# H3BR20.net
KiCad netlist of a schematic drawn in EAGLE
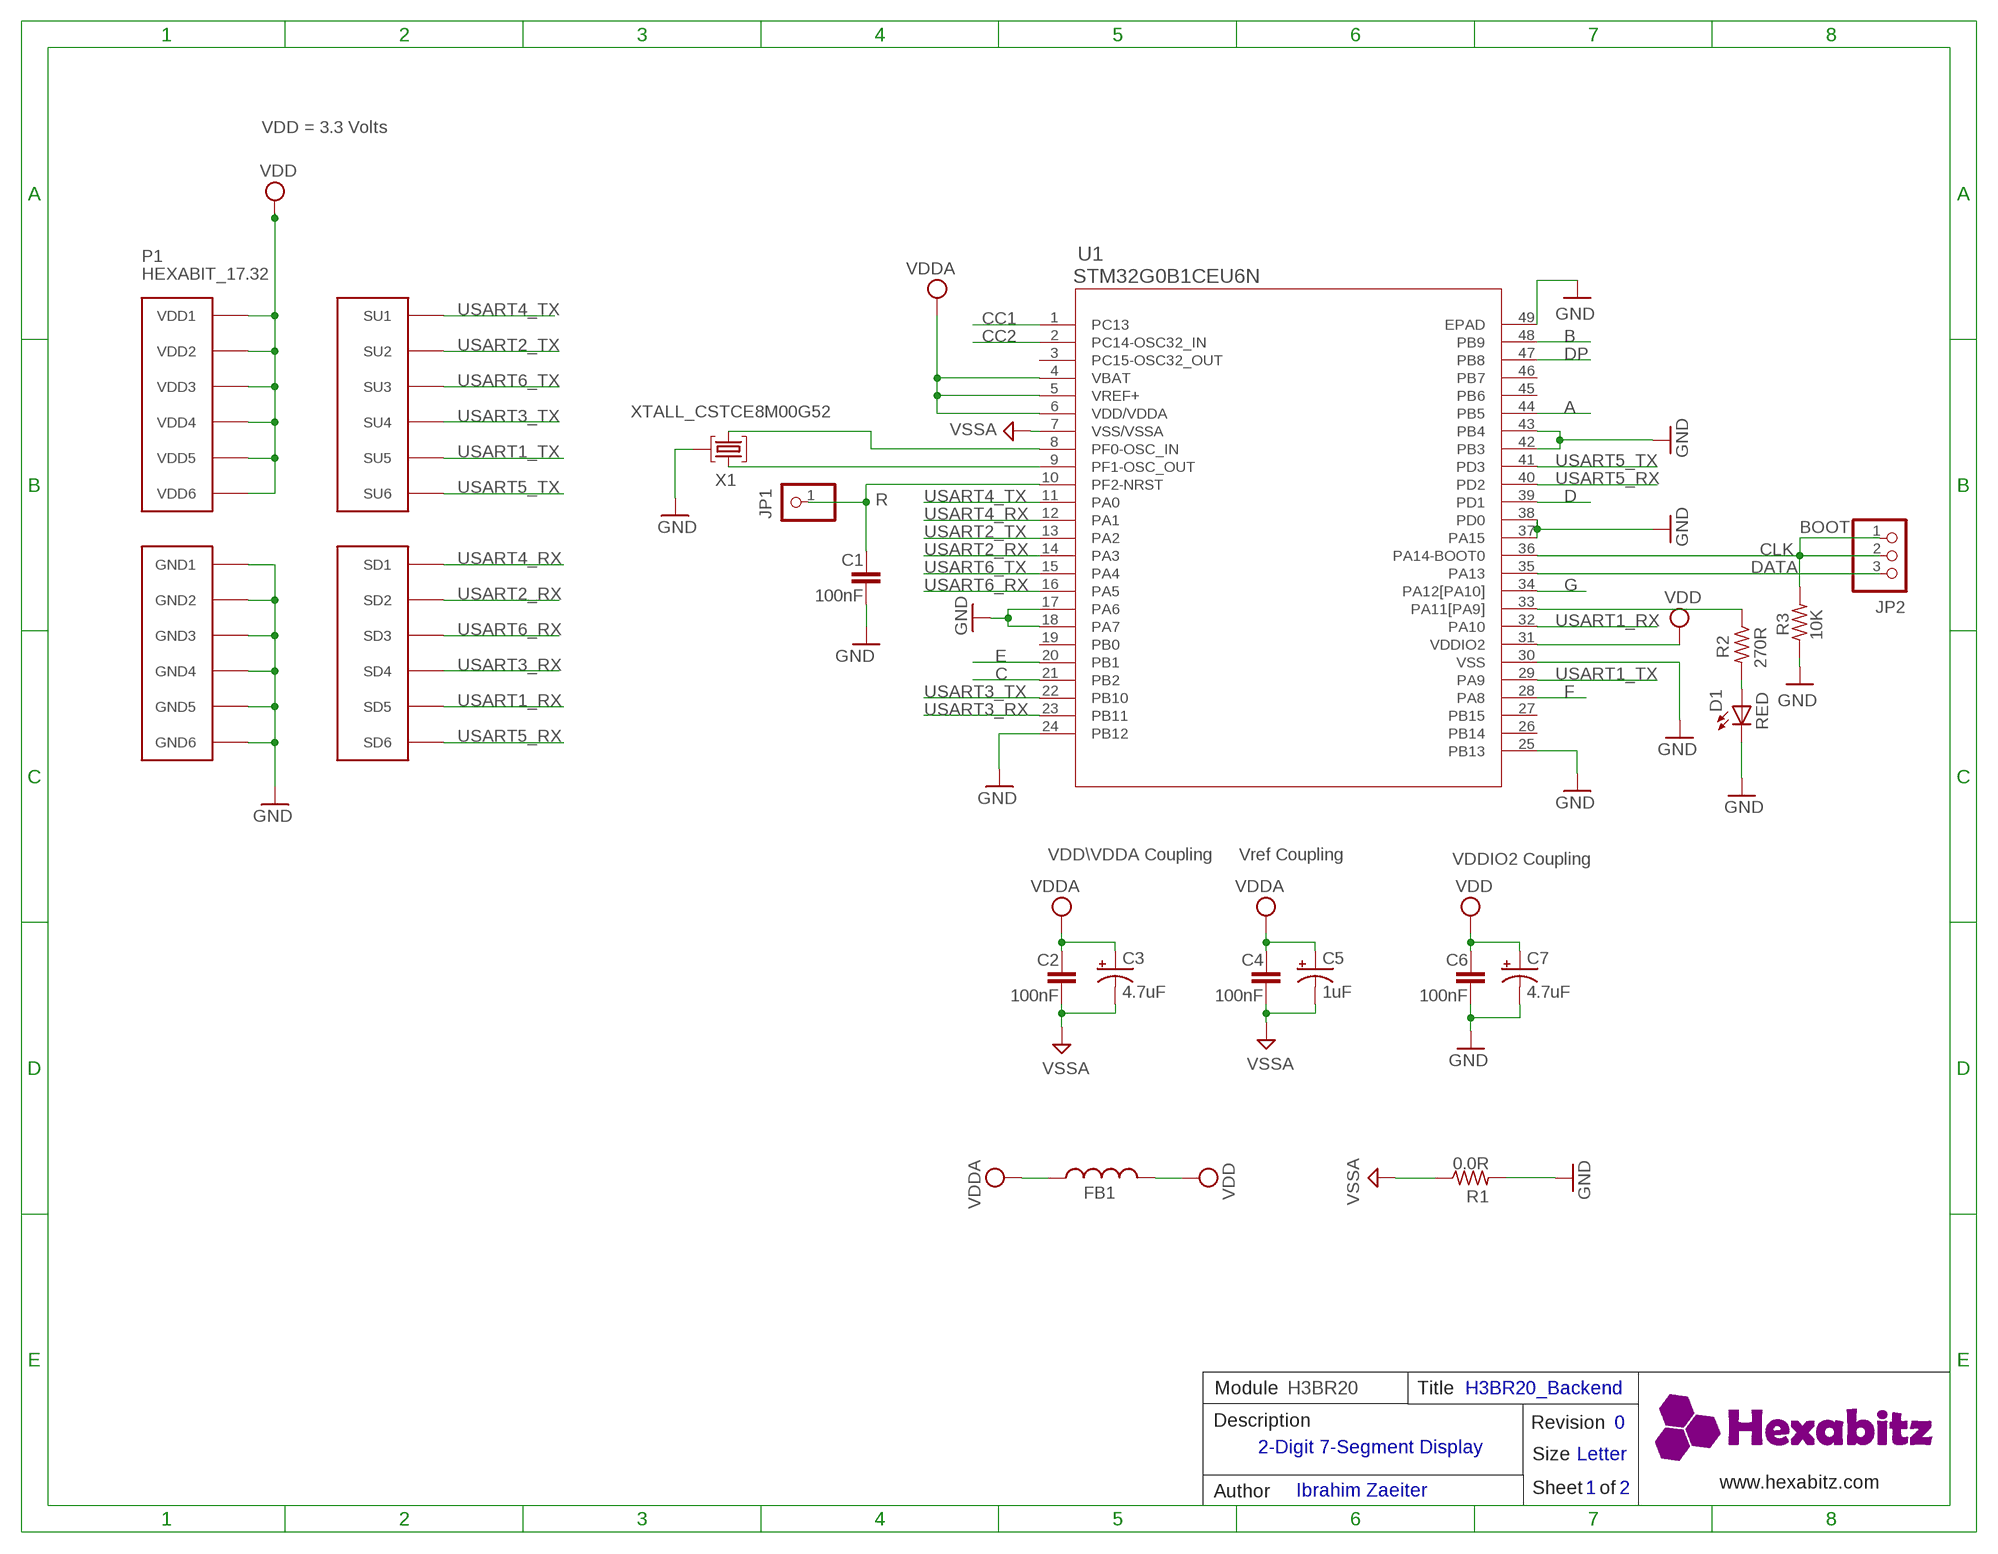
[diagram p0: schematic, sheet 1]
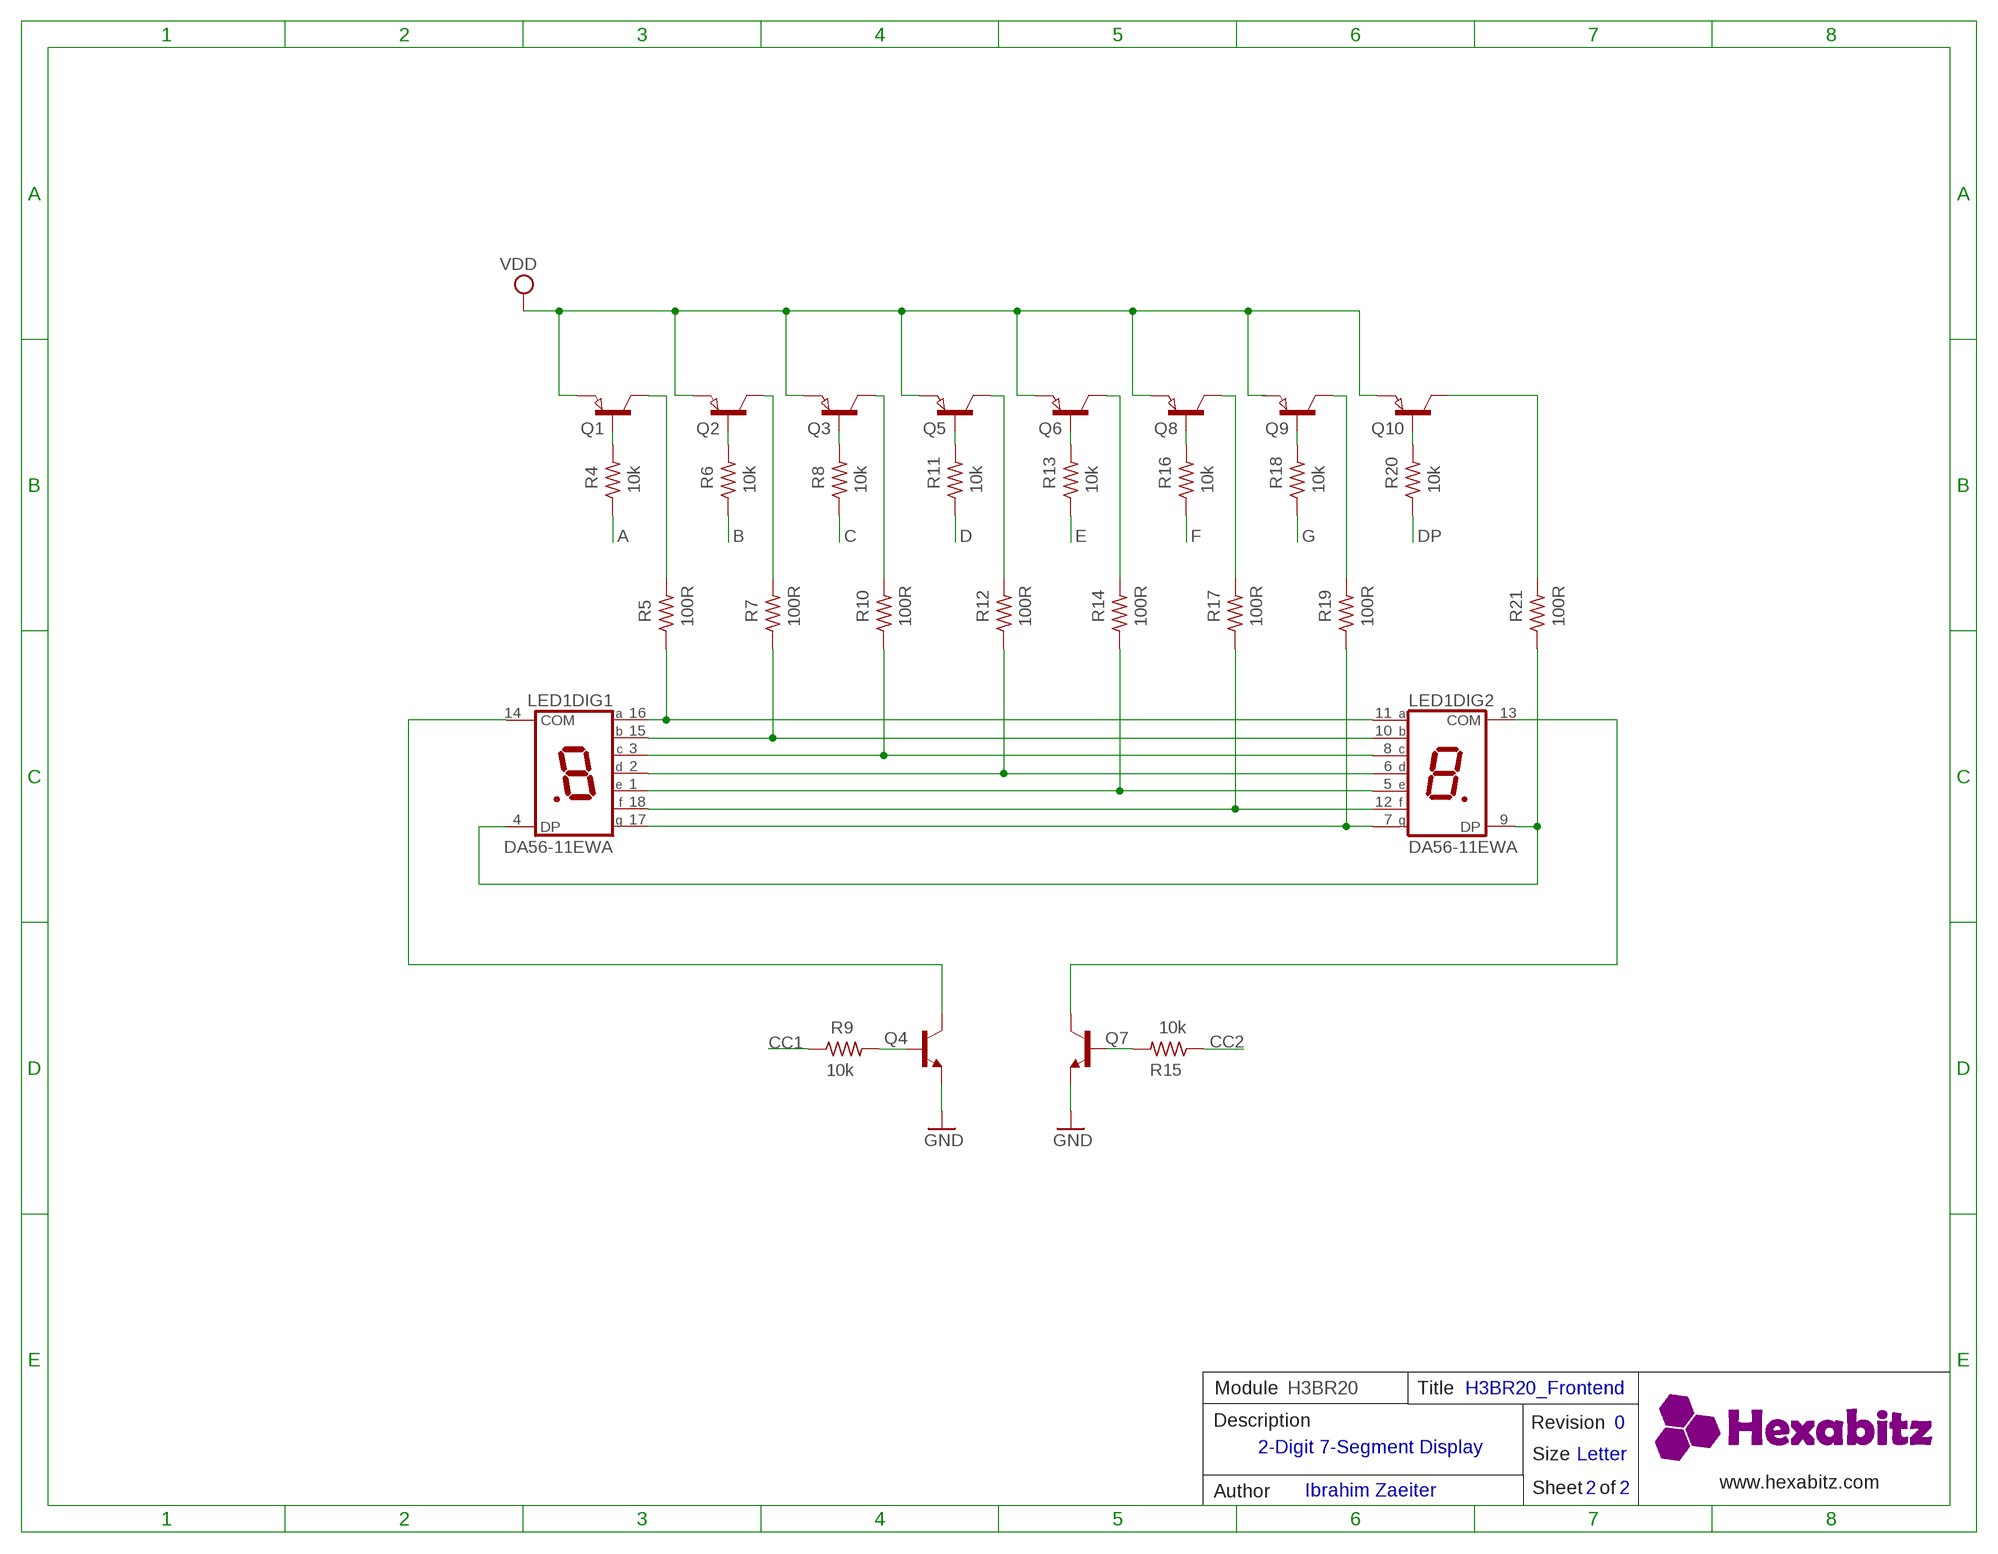
[diagram p1: schematic, sheet 2]

(export (version "E")
  (design (tool "Eeschema 10.0.6"))
  (components
    (comp (ref "LED1")
      (value "DA56-11EWA")
      (footprint "eagle-import:DA56")
      (fields (field (name "MF") "Lite-On") (field (name "MPN") "LTD-6940HR"))
      (libsource (lib "eagle-import") (part "DA56-11EWA"))
    )
    (comp (ref "Q1")
      (value "SEMICON-SMD-IPC_PNP-TRANSISTOR_SOT23")
      (footprint "eagle-import:SEMICON-SMD-IPC_SOT23")
      (libsource (lib "eagle-import") (part "SEMICON-SMD-IPC_PNP-TRANSISTOR_SOT23"))
    )
    (comp (ref "Q2")
      (value "SEMICON-SMD-IPC_PNP-TRANSISTOR_SOT23")
      (footprint "eagle-import:SEMICON-SMD-IPC_SOT23")
      (libsource (lib "eagle-import") (part "SEMICON-SMD-IPC_PNP-TRANSISTOR_SOT23"))
    )
    (comp (ref "Q3")
      (value "SEMICON-SMD-IPC_PNP-TRANSISTOR_SOT23")
      (footprint "eagle-import:SEMICON-SMD-IPC_SOT23")
      (libsource (lib "eagle-import") (part "SEMICON-SMD-IPC_PNP-TRANSISTOR_SOT23"))
    )
    (comp (ref "Q4")
      (value "MMBT3904LT1")
      (footprint "eagle-import:MMBT3904LT1")
      (libsource (lib "eagle-import") (part "MMBT3904LT1"))
    )
    (comp (ref "Q5")
      (value "SEMICON-SMD-IPC_PNP-TRANSISTOR_SOT23")
      (footprint "eagle-import:SEMICON-SMD-IPC_SOT23")
      (libsource (lib "eagle-import") (part "SEMICON-SMD-IPC_PNP-TRANSISTOR_SOT23"))
    )
    (comp (ref "Q6")
      (value "SEMICON-SMD-IPC_PNP-TRANSISTOR_SOT23")
      (footprint "eagle-import:SEMICON-SMD-IPC_SOT23")
      (libsource (lib "eagle-import") (part "SEMICON-SMD-IPC_PNP-TRANSISTOR_SOT23"))
    )
    (comp (ref "Q7")
      (value "MMBT3904LT1")
      (footprint "eagle-import:MMBT3904LT1")
      (libsource (lib "eagle-import") (part "MMBT3904LT1"))
    )
    (comp (ref "Q8")
      (value "SEMICON-SMD-IPC_PNP-TRANSISTOR_SOT23")
      (footprint "eagle-import:SEMICON-SMD-IPC_SOT23")
      (libsource (lib "eagle-import") (part "SEMICON-SMD-IPC_PNP-TRANSISTOR_SOT23"))
    )
    (comp (ref "Q9")
      (value "SEMICON-SMD-IPC_PNP-TRANSISTOR_SOT23")
      (footprint "eagle-import:SEMICON-SMD-IPC_SOT23")
      (libsource (lib "eagle-import") (part "SEMICON-SMD-IPC_PNP-TRANSISTOR_SOT23"))
    )
    (comp (ref "Q10")
      (value "SEMICON-SMD-IPC_PNP-TRANSISTOR_SOT23")
      (footprint "eagle-import:SEMICON-SMD-IPC_SOT23")
      (libsource (lib "eagle-import") (part "SEMICON-SMD-IPC_PNP-TRANSISTOR_SOT23"))
    )
    (comp (ref "R4")
      (value "10k")
      (footprint "eagle-import:R-0402")
      (libsource (lib "eagle-import") (part "R-0402"))
    )
    (comp (ref "R5")
      (value "100R")
      (footprint "eagle-import:R-0402")
      (libsource (lib "eagle-import") (part "R-0402"))
    )
    (comp (ref "R6")
      (value "10k")
      (footprint "eagle-import:R-0402")
      (libsource (lib "eagle-import") (part "R-0402"))
    )
    (comp (ref "R7")
      (value "100R")
      (footprint "eagle-import:R-0402")
      (libsource (lib "eagle-import") (part "R-0402"))
    )
    (comp (ref "R8")
      (value "10k")
      (footprint "eagle-import:R-0402")
      (libsource (lib "eagle-import") (part "R-0402"))
    )
    (comp (ref "R9")
      (value "10k")
      (footprint "eagle-import:R-0402")
      (libsource (lib "eagle-import") (part "R-0402"))
    )
    (comp (ref "R10")
      (value "100R")
      (footprint "eagle-import:R-0402")
      (libsource (lib "eagle-import") (part "R-0402"))
    )
    (comp (ref "R11")
      (value "10k")
      (footprint "eagle-import:R-0402")
      (libsource (lib "eagle-import") (part "R-0402"))
    )
    (comp (ref "R12")
      (value "100R")
      (footprint "eagle-import:R-0402")
      (libsource (lib "eagle-import") (part "R-0402"))
    )
    (comp (ref "R13")
      (value "10k")
      (footprint "eagle-import:R-0402")
      (libsource (lib "eagle-import") (part "R-0402"))
    )
    (comp (ref "R14")
      (value "100R")
      (footprint "eagle-import:R-0402")
      (libsource (lib "eagle-import") (part "R-0402"))
    )
    (comp (ref "R15")
      (value "10k")
      (footprint "eagle-import:R-0402")
      (libsource (lib "eagle-import") (part "R-0402"))
    )
    (comp (ref "R16")
      (value "10k")
      (footprint "eagle-import:R-0402")
      (libsource (lib "eagle-import") (part "R-0402"))
    )
    (comp (ref "R17")
      (value "100R")
      (footprint "eagle-import:R-0402")
      (libsource (lib "eagle-import") (part "R-0402"))
    )
    (comp (ref "R18")
      (value "10k")
      (footprint "eagle-import:R-0402")
      (libsource (lib "eagle-import") (part "R-0402"))
    )
    (comp (ref "R19")
      (value "100R")
      (footprint "eagle-import:R-0402")
      (libsource (lib "eagle-import") (part "R-0402"))
    )
    (comp (ref "R20")
      (value "10k")
      (footprint "eagle-import:R-0402")
      (libsource (lib "eagle-import") (part "R-0402"))
    )
    (comp (ref "R21")
      (value "100R")
      (footprint "eagle-import:R-0402")
      (libsource (lib "eagle-import") (part "R-0402"))
    )
    (comp (ref "C1")
      (value "100nF")
      (footprint "eagle-import:C-0402")
      (libsource (lib "eagle-import") (part "C-0402"))
    )
    (comp (ref "C2")
      (value "100nF")
      (footprint "eagle-import:C-0402")
      (libsource (lib "eagle-import") (part "C-0402"))
    )
    (comp (ref "C3")
      (value "4.7uF")
      (footprint "eagle-import:C-0805-POL")
      (libsource (lib "eagle-import") (part "C-0805-POL"))
    )
    (comp (ref "C4")
      (value "100nF")
      (footprint "eagle-import:C-0402")
      (libsource (lib "eagle-import") (part "C-0402"))
    )
    (comp (ref "C5")
      (value "1uF")
      (footprint "eagle-import:C-0805-POL")
      (libsource (lib "eagle-import") (part "C-0805-POL"))
    )
    (comp (ref "C6")
      (value "100nF")
      (footprint "eagle-import:C-0402")
      (libsource (lib "eagle-import") (part "C-0402"))
    )
    (comp (ref "C7")
      (value "4.7uF")
      (footprint "eagle-import:C-0805-POL")
      (libsource (lib "eagle-import") (part "C-0805-POL"))
    )
    (comp (ref "D1")
      (value "RED")
      (footprint "eagle-import:VLMS1300-GS08")
      (fields
        (field (name "MPN") "VLMS1300-GS08")
        (field (name "MFN") "Vishay")
        (field (name "MPN_1") "VLMS1300-GS08")
        (field (name "OCTOPART_URL") "https://octopart.com/vlms1300-gs08-vishay-21709201?r=sp&s=_gcP4_q8T1SC6PJQPTQ9yA")
      )
      (libsource (lib "eagle-import") (part "VLMS1300-GS08"))
    )
    (comp (ref "FB1")
      (value "FB-0603")
      (footprint "eagle-import:FB-0603")
      (libsource (lib "eagle-import") (part "FB-0603"))
    )
    (comp (ref "JP1")
      (value "R")
      (footprint "eagle-import:1X01")
      (fields (field (name "MPN") "87227-1"))
      (libsource (lib "eagle-import") (part "PINHD-1X1"))
    )
    (comp (ref "JP2")
      (value "PINHD-1X3")
      (footprint "eagle-import:1X03")
      (libsource (lib "eagle-import") (part "PINHD-1X3"))
    )
    (comp (ref "P1")
      (value "HEXABIT_17.32")
      (footprint "eagle-import:HEXABIT_17.32")
      (libsource (lib "eagle-import") (part "HEXABIT_?17.32"))
    )
    (comp (ref "R1")
      (value "0.0R")
      (footprint "eagle-import:R-0402")
      (libsource (lib "eagle-import") (part "R-0402"))
    )
    (comp (ref "R2")
      (value "270R")
      (footprint "eagle-import:R-0603")
      (libsource (lib "eagle-import") (part "R-0603"))
    )
    (comp (ref "R3")
      (value "10K")
      (footprint "eagle-import:R-0402")
      (libsource (lib "eagle-import") (part "R-0402"))
    )
    (comp (ref "U1")
      (value "STM32G0B1CEU6N")
      (footprint "eagle-import:QFN_B1CEU6_STM-L")
      (libsource (lib "eagle-import") (part "STM32G0B1CEU6N"))
    )
    (comp (ref "X1")
      (value "XTALL_CSTCE8M00G52")
      (footprint "eagle-import:XTALL_CSTCE8M00G52")
      (fields (field (name "MPN") "CSTCE8M00G52Z-R0"))
      (libsource (lib "eagle-import") (part "XTALL_CSTCE8M00G52"))
    )
  )
  (nets
    (net (code "1") (name "A") (class "Default")
      (node (ref "R4") (pin "1") (pinfunction "1_1") (pintype "passive"))
      (node (ref "U1") (pin "44") (pinfunction "PB5_44") (pintype "bidirectional"))
    )
    (net (code "2") (name "B") (class "Default")
      (node (ref "R6") (pin "1") (pinfunction "1_1") (pintype "passive"))
      (node (ref "U1") (pin "48") (pinfunction "PB9_48") (pintype "bidirectional"))
    )
    (net (code "3") (name "C") (class "Default")
      (node (ref "R8") (pin "1") (pinfunction "1_1") (pintype "passive"))
      (node (ref "U1") (pin "21") (pinfunction "PB2_21") (pintype "bidirectional"))
    )
    (net (code "4") (name "CC1") (class "Default")
      (node (ref "R9") (pin "1") (pinfunction "1_1") (pintype "passive"))
      (node (ref "U1") (pin "1") (pinfunction "PC13_1") (pintype "bidirectional"))
    )
    (net (code "5") (name "CC2") (class "Default")
      (node (ref "R15") (pin "1") (pinfunction "1_1") (pintype "passive"))
      (node (ref "U1") (pin "2") (pinfunction "PC14-OSC32_IN_2") (pintype "bidirectional"))
    )
    (net (code "6") (name "CLK") (class "Default")
      (node (ref "JP2") (pin "1") (pinfunction "1_1") (pintype "passive"))
      (node (ref "JP2") (pin "2") (pinfunction "2_2") (pintype "passive"))
      (node (ref "R3") (pin "2") (pinfunction "2_2") (pintype "passive"))
      (node (ref "U1") (pin "36") (pinfunction "PA14-BOOT0_36") (pintype "bidirectional"))
    )
    (net (code "7") (name "D") (class "Default")
      (node (ref "R11") (pin "1") (pinfunction "1_1") (pintype "passive"))
      (node (ref "U1") (pin "39") (pinfunction "PD1_39") (pintype "bidirectional"))
    )
    (net (code "8") (name "DATA") (class "Default")
      (node (ref "JP2") (pin "3") (pinfunction "3_3") (pintype "passive"))
      (node (ref "U1") (pin "35") (pinfunction "PA13_35") (pintype "bidirectional"))
    )
    (net (code "9") (name "DP") (class "Default")
      (node (ref "R20") (pin "1") (pinfunction "1_1") (pintype "passive"))
      (node (ref "U1") (pin "47") (pinfunction "PB8_47") (pintype "bidirectional"))
    )
    (net (code "10") (name "E") (class "Default")
      (node (ref "R13") (pin "1") (pinfunction "1_1") (pintype "passive"))
      (node (ref "U1") (pin "20") (pinfunction "PB1_20") (pintype "bidirectional"))
    )
    (net (code "11") (name "F") (class "Default")
      (node (ref "R16") (pin "1") (pinfunction "1_1") (pintype "passive"))
      (node (ref "U1") (pin "28") (pinfunction "PA8_28") (pintype "bidirectional"))
    )
    (net (code "12") (name "G") (class "Default")
      (node (ref "R18") (pin "1") (pinfunction "1_1") (pintype "passive"))
      (node (ref "U1") (pin "34") (pinfunction "PA12[PA10]_34") (pintype "bidirectional"))
    )
    (net (code "13") (name "GND") (class "Default")
      (node (ref "C1") (pin "2") (pinfunction "2_2") (pintype "passive"))
      (node (ref "C6") (pin "2") (pinfunction "2_2") (pintype "passive"))
      (node (ref "C7") (pin "2") (pinfunction "-_2") (pintype "passive"))
      (node (ref "D1") (pin "C") (pinfunction "C_C") (pintype "passive"))
      (node (ref "P1") (pin "PAD_PD10") (pinfunction "GND4_PAD_PD10") (pintype "power_in"))
      (node (ref "P1") (pin "PAD_PD11") (pinfunction "GND5_PAD_PD11") (pintype "power_in"))
      (node (ref "P1") (pin "PAD_PD12") (pinfunction "GND6_PAD_PD12") (pintype "power_in"))
      (node (ref "P1") (pin "PAD_PD7") (pinfunction "GND1_PAD_PD7") (pintype "power_in"))
      (node (ref "P1") (pin "PAD_PD8") (pinfunction "GND2_PAD_PD8") (pintype "power_in"))
      (node (ref "P1") (pin "PAD_PD9") (pinfunction "GND3_PAD_PD9") (pintype "power_in"))
      (node (ref "Q4") (pin "2") (pinfunction "E_2") (pintype "passive"))
      (node (ref "Q7") (pin "2") (pinfunction "E_2") (pintype "passive"))
      (node (ref "R1") (pin "2") (pinfunction "2_2") (pintype "passive"))
      (node (ref "R3") (pin "1") (pinfunction "1_1") (pintype "passive"))
      (node (ref "U1") (pin "17") (pinfunction "PA6_17") (pintype "bidirectional"))
      (node (ref "U1") (pin "18") (pinfunction "PA7_18") (pintype "bidirectional"))
      (node (ref "U1") (pin "24") (pinfunction "PB12_24") (pintype "bidirectional"))
      (node (ref "U1") (pin "25") (pinfunction "PB13_25") (pintype "bidirectional"))
      (node (ref "U1") (pin "30") (pinfunction "VSS_30") (pintype "passive"))
      (node (ref "U1") (pin "37") (pinfunction "PA15_37") (pintype "bidirectional"))
      (node (ref "U1") (pin "38") (pinfunction "PD0_38") (pintype "bidirectional"))
      (node (ref "U1") (pin "42") (pinfunction "PB3_42") (pintype "bidirectional"))
      (node (ref "U1") (pin "43") (pinfunction "PB4_43") (pintype "bidirectional"))
      (node (ref "U1") (pin "49") (pinfunction "EPAD_49") (pintype "passive"))
      (node (ref "X1") (pin "P$2") (pinfunction "2_P$2") (pintype "passive"))
    )
    (net (code "14") (name "Net-(D1-PadA)") (class "Default")
      (node (ref "D1") (pin "A") (pinfunction "A_A") (pintype "passive"))
      (node (ref "R2") (pin "2") (pinfunction "2_2") (pintype "passive"))
    )
    (net (code "15") (name "Net-(LED1A-A)") (class "Default")
      (node (ref "LED1") (pin "11") (pinfunction "A_11") (pintype "passive"))
      (node (ref "LED1") (pin "16") (pinfunction "A_16") (pintype "passive"))
      (node (ref "R5") (pin "1") (pinfunction "1_1") (pintype "passive"))
    )
    (net (code "16") (name "Net-(LED1A-B)") (class "Default")
      (node (ref "LED1") (pin "10") (pinfunction "B_10") (pintype "passive"))
      (node (ref "LED1") (pin "15") (pinfunction "B_15") (pintype "passive"))
      (node (ref "R7") (pin "1") (pinfunction "1_1") (pintype "passive"))
    )
    (net (code "17") (name "Net-(LED1A-C)") (class "Default")
      (node (ref "LED1") (pin "3") (pinfunction "C_3") (pintype "passive"))
      (node (ref "LED1") (pin "8") (pinfunction "C_8") (pintype "passive"))
      (node (ref "R10") (pin "1") (pinfunction "1_1") (pintype "passive"))
    )
    (net (code "18") (name "Net-(LED1A-COM)") (class "Default")
      (node (ref "LED1") (pin "14") (pinfunction "COM_14") (pintype "passive"))
      (node (ref "Q4") (pin "3") (pinfunction "C_3") (pintype "passive"))
    )
    (net (code "19") (name "Net-(LED1A-D)") (class "Default")
      (node (ref "LED1") (pin "2") (pinfunction "D_2") (pintype "passive"))
      (node (ref "LED1") (pin "6") (pinfunction "D_6") (pintype "passive"))
      (node (ref "R12") (pin "1") (pinfunction "1_1") (pintype "passive"))
    )
    (net (code "20") (name "Net-(LED1A-DP)") (class "Default")
      (node (ref "LED1") (pin "4") (pinfunction "DP_4") (pintype "passive"))
      (node (ref "LED1") (pin "9") (pinfunction "DP_9") (pintype "passive"))
      (node (ref "R21") (pin "1") (pinfunction "1_1") (pintype "passive"))
    )
    (net (code "21") (name "Net-(LED1A-E)") (class "Default")
      (node (ref "LED1") (pin "1") (pinfunction "E_1") (pintype "passive"))
      (node (ref "LED1") (pin "5") (pinfunction "E_5") (pintype "passive"))
      (node (ref "R14") (pin "1") (pinfunction "1_1") (pintype "passive"))
    )
    (net (code "22") (name "Net-(LED1A-F)") (class "Default")
      (node (ref "LED1") (pin "12") (pinfunction "F_12") (pintype "passive"))
      (node (ref "LED1") (pin "18") (pinfunction "F_18") (pintype "passive"))
      (node (ref "R17") (pin "1") (pinfunction "1_1") (pintype "passive"))
    )
    (net (code "23") (name "Net-(LED1A-G)") (class "Default")
      (node (ref "LED1") (pin "17") (pinfunction "G_17") (pintype "passive"))
      (node (ref "LED1") (pin "7") (pinfunction "G_7") (pintype "passive"))
      (node (ref "R19") (pin "1") (pinfunction "1_1") (pintype "passive"))
    )
    (net (code "24") (name "Net-(LED1B-COM)") (class "Default")
      (node (ref "LED1") (pin "13") (pinfunction "COM_13") (pintype "passive"))
      (node (ref "Q7") (pin "3") (pinfunction "C_3") (pintype "passive"))
    )
    (net (code "25") (name "Net-(Q1-B)") (class "Default")
      (node (ref "Q1") (pin "1") (pinfunction "B_1") (pintype "passive"))
      (node (ref "R4") (pin "2") (pinfunction "2_2") (pintype "passive"))
    )
    (net (code "26") (name "Net-(Q1-C)") (class "Default")
      (node (ref "Q1") (pin "3") (pinfunction "C_3") (pintype "passive"))
      (node (ref "R5") (pin "2") (pinfunction "2_2") (pintype "passive"))
    )
    (net (code "27") (name "Net-(Q2-B)") (class "Default")
      (node (ref "Q2") (pin "1") (pinfunction "B_1") (pintype "passive"))
      (node (ref "R6") (pin "2") (pinfunction "2_2") (pintype "passive"))
    )
    (net (code "28") (name "Net-(Q2-C)") (class "Default")
      (node (ref "Q2") (pin "3") (pinfunction "C_3") (pintype "passive"))
      (node (ref "R7") (pin "2") (pinfunction "2_2") (pintype "passive"))
    )
    (net (code "29") (name "Net-(Q3-B)") (class "Default")
      (node (ref "Q3") (pin "1") (pinfunction "B_1") (pintype "passive"))
      (node (ref "R8") (pin "2") (pinfunction "2_2") (pintype "passive"))
    )
    (net (code "30") (name "Net-(Q3-C)") (class "Default")
      (node (ref "Q3") (pin "3") (pinfunction "C_3") (pintype "passive"))
      (node (ref "R10") (pin "2") (pinfunction "2_2") (pintype "passive"))
    )
    (net (code "31") (name "Net-(Q4-B)") (class "Default")
      (node (ref "Q4") (pin "1") (pinfunction "B_1") (pintype "passive"))
      (node (ref "R9") (pin "2") (pinfunction "2_2") (pintype "passive"))
    )
    (net (code "32") (name "Net-(Q5-B)") (class "Default")
      (node (ref "Q5") (pin "1") (pinfunction "B_1") (pintype "passive"))
      (node (ref "R11") (pin "2") (pinfunction "2_2") (pintype "passive"))
    )
    (net (code "33") (name "Net-(Q5-C)") (class "Default")
      (node (ref "Q5") (pin "3") (pinfunction "C_3") (pintype "passive"))
      (node (ref "R12") (pin "2") (pinfunction "2_2") (pintype "passive"))
    )
    (net (code "34") (name "Net-(Q6-B)") (class "Default")
      (node (ref "Q6") (pin "1") (pinfunction "B_1") (pintype "passive"))
      (node (ref "R13") (pin "2") (pinfunction "2_2") (pintype "passive"))
    )
    (net (code "35") (name "Net-(Q6-C)") (class "Default")
      (node (ref "Q6") (pin "3") (pinfunction "C_3") (pintype "passive"))
      (node (ref "R14") (pin "2") (pinfunction "2_2") (pintype "passive"))
    )
    (net (code "36") (name "Net-(Q7-B)") (class "Default")
      (node (ref "Q7") (pin "1") (pinfunction "B_1") (pintype "passive"))
      (node (ref "R15") (pin "2") (pinfunction "2_2") (pintype "passive"))
    )
    (net (code "37") (name "Net-(Q8-B)") (class "Default")
      (node (ref "Q8") (pin "1") (pinfunction "B_1") (pintype "passive"))
      (node (ref "R16") (pin "2") (pinfunction "2_2") (pintype "passive"))
    )
    (net (code "38") (name "Net-(Q8-C)") (class "Default")
      (node (ref "Q8") (pin "3") (pinfunction "C_3") (pintype "passive"))
      (node (ref "R17") (pin "2") (pinfunction "2_2") (pintype "passive"))
    )
    (net (code "39") (name "Net-(Q9-B)") (class "Default")
      (node (ref "Q9") (pin "1") (pinfunction "B_1") (pintype "passive"))
      (node (ref "R18") (pin "2") (pinfunction "2_2") (pintype "passive"))
    )
    (net (code "40") (name "Net-(Q9-C)") (class "Default")
      (node (ref "Q9") (pin "3") (pinfunction "C_3") (pintype "passive"))
      (node (ref "R19") (pin "2") (pinfunction "2_2") (pintype "passive"))
    )
    (net (code "41") (name "Net-(Q10-B)") (class "Default")
      (node (ref "Q10") (pin "1") (pinfunction "B_1") (pintype "passive"))
      (node (ref "R20") (pin "2") (pinfunction "2_2") (pintype "passive"))
    )
    (net (code "42") (name "Net-(Q10-C)") (class "Default")
      (node (ref "Q10") (pin "3") (pinfunction "C_3") (pintype "passive"))
      (node (ref "R21") (pin "2") (pinfunction "2_2") (pintype "passive"))
    )
    (net (code "43") (name "Net-(U1-PA11[PA9])") (class "Default")
      (node (ref "R2") (pin "1") (pinfunction "1_1") (pintype "passive"))
      (node (ref "U1") (pin "33") (pinfunction "PA11[PA9]_33") (pintype "bidirectional"))
    )
    (net (code "44") (name "Net-(U1-PF0-OSC_IN)") (class "Default")
      (node (ref "U1") (pin "8") (pinfunction "PF0-OSC_IN_8") (pintype "bidirectional"))
      (node (ref "X1") (pin "P$3") (pinfunction "3_P$3") (pintype "passive"))
    )
    (net (code "45") (name "Net-(U1-PF1-OSC_OUT)") (class "Default")
      (node (ref "U1") (pin "9") (pinfunction "PF1-OSC_OUT_9") (pintype "bidirectional"))
      (node (ref "X1") (pin "P$1") (pinfunction "1_P$1") (pintype "passive"))
    )
    (net (code "46") (name "Net-(U1-PF2-NRST)") (class "Default")
      (node (ref "C1") (pin "1") (pinfunction "1_1") (pintype "passive"))
      (node (ref "JP1") (pin "1") (pinfunction "1_1") (pintype "passive"))
      (node (ref "U1") (pin "10") (pinfunction "PF2-NRST_10") (pintype "bidirectional"))
    )
    (net (code "47") (name "USART1_RX") (class "Default")
      (node (ref "P1") (pin "PAD_PD5") (pinfunction "SD5_PAD_PD5") (pintype "bidirectional"))
      (node (ref "U1") (pin "32") (pinfunction "PA10_32") (pintype "bidirectional"))
    )
    (net (code "48") (name "USART1_TX") (class "Default")
      (node (ref "P1") (pin "PAD_PU5") (pinfunction "SU5_PAD_PU5") (pintype "bidirectional"))
      (node (ref "U1") (pin "29") (pinfunction "PA9_29") (pintype "bidirectional"))
    )
    (net (code "49") (name "USART2_RX") (class "Default")
      (node (ref "P1") (pin "PAD_PD2") (pinfunction "SD2_PAD_PD2") (pintype "bidirectional"))
      (node (ref "U1") (pin "14") (pinfunction "PA3_14") (pintype "bidirectional"))
    )
    (net (code "50") (name "USART2_TX") (class "Default")
      (node (ref "P1") (pin "PAD_PU2") (pinfunction "SU2_PAD_PU2") (pintype "bidirectional"))
      (node (ref "U1") (pin "13") (pinfunction "PA2_13") (pintype "bidirectional"))
    )
    (net (code "51") (name "USART3_RX") (class "Default")
      (node (ref "P1") (pin "PAD_PD4") (pinfunction "SD4_PAD_PD4") (pintype "bidirectional"))
      (node (ref "U1") (pin "23") (pinfunction "PB11_23") (pintype "bidirectional"))
    )
    (net (code "52") (name "USART3_TX") (class "Default")
      (node (ref "P1") (pin "PAD_PU4") (pinfunction "SU4_PAD_PU4") (pintype "bidirectional"))
      (node (ref "U1") (pin "22") (pinfunction "PB10_22") (pintype "bidirectional"))
    )
    (net (code "53") (name "USART4_RX") (class "Default")
      (node (ref "P1") (pin "PAD_PD1") (pinfunction "SD1_PAD_PD1") (pintype "bidirectional"))
      (node (ref "U1") (pin "12") (pinfunction "PA1_12") (pintype "bidirectional"))
    )
    (net (code "54") (name "USART4_TX") (class "Default")
      (node (ref "P1") (pin "PAD_PU1") (pinfunction "SU1_PAD_PU1") (pintype "bidirectional"))
      (node (ref "U1") (pin "11") (pinfunction "PA0_11") (pintype "bidirectional"))
    )
    (net (code "55") (name "USART5_RX") (class "Default")
      (node (ref "P1") (pin "PAD_PD6") (pinfunction "SD6_PAD_PD6") (pintype "bidirectional"))
      (node (ref "U1") (pin "40") (pinfunction "PD2_40") (pintype "bidirectional"))
    )
    (net (code "56") (name "USART5_TX") (class "Default")
      (node (ref "P1") (pin "PAD_PU6") (pinfunction "SU6_PAD_PU6") (pintype "bidirectional"))
      (node (ref "U1") (pin "41") (pinfunction "PD3_41") (pintype "bidirectional"))
    )
    (net (code "57") (name "USART6_RX") (class "Default")
      (node (ref "P1") (pin "PAD_PD3") (pinfunction "SD3_PAD_PD3") (pintype "bidirectional"))
      (node (ref "U1") (pin "16") (pinfunction "PA5_16") (pintype "bidirectional"))
    )
    (net (code "58") (name "USART6_TX") (class "Default")
      (node (ref "P1") (pin "PAD_PU3") (pinfunction "SU3_PAD_PU3") (pintype "bidirectional"))
      (node (ref "U1") (pin "15") (pinfunction "PA4_15") (pintype "bidirectional"))
    )
    (net (code "59") (name "VDD") (class "Default")
      (node (ref "C6") (pin "1") (pinfunction "1_1") (pintype "passive"))
      (node (ref "C7") (pin "1") (pinfunction "+_1") (pintype "passive"))
      (node (ref "FB1") (pin "2") (pinfunction "2_2") (pintype "passive"))
      (node (ref "P1") (pin "PAD_PU10") (pinfunction "VDD4_PAD_PU10") (pintype "power_in"))
      (node (ref "P1") (pin "PAD_PU11") (pinfunction "VDD5_PAD_PU11") (pintype "power_in"))
      (node (ref "P1") (pin "PAD_PU12") (pinfunction "VDD6_PAD_PU12") (pintype "power_in"))
      (node (ref "P1") (pin "PAD_PU7") (pinfunction "VDD1_PAD_PU7") (pintype "power_in"))
      (node (ref "P1") (pin "PAD_PU8") (pinfunction "VDD2_PAD_PU8") (pintype "power_in"))
      (node (ref "P1") (pin "PAD_PU9") (pinfunction "VDD3_PAD_PU9") (pintype "power_in"))
      (node (ref "Q1") (pin "2") (pinfunction "E_2") (pintype "passive"))
      (node (ref "Q10") (pin "2") (pinfunction "E_2") (pintype "passive"))
      (node (ref "Q2") (pin "2") (pinfunction "E_2") (pintype "passive"))
      (node (ref "Q3") (pin "2") (pinfunction "E_2") (pintype "passive"))
      (node (ref "Q5") (pin "2") (pinfunction "E_2") (pintype "passive"))
      (node (ref "Q6") (pin "2") (pinfunction "E_2") (pintype "passive"))
      (node (ref "Q8") (pin "2") (pinfunction "E_2") (pintype "passive"))
      (node (ref "Q9") (pin "2") (pinfunction "E_2") (pintype "passive"))
      (node (ref "U1") (pin "31") (pinfunction "VDDIO2_31") (pintype "power_in"))
    )
    (net (code "60") (name "VDDA") (class "Default")
      (node (ref "C2") (pin "1") (pinfunction "1_1") (pintype "passive"))
      (node (ref "C3") (pin "1") (pinfunction "+_1") (pintype "passive"))
      (node (ref "C4") (pin "1") (pinfunction "1_1") (pintype "passive"))
      (node (ref "C5") (pin "1") (pinfunction "+_1") (pintype "passive"))
      (node (ref "FB1") (pin "1") (pinfunction "1_1") (pintype "passive"))
      (node (ref "U1") (pin "4") (pinfunction "VBAT_4") (pintype "power_in"))
      (node (ref "U1") (pin "5") (pinfunction "VREF+_5") (pintype "power_in"))
      (node (ref "U1") (pin "6") (pinfunction "VDD/VDDA_6") (pintype "power_in"))
    )
    (net (code "61") (name "VSSA") (class "Default")
      (node (ref "C2") (pin "2") (pinfunction "2_2") (pintype "passive"))
      (node (ref "C3") (pin "2") (pinfunction "-_2") (pintype "passive"))
      (node (ref "C4") (pin "2") (pinfunction "2_2") (pintype "passive"))
      (node (ref "C5") (pin "2") (pinfunction "-_2") (pintype "passive"))
      (node (ref "R1") (pin "1") (pinfunction "1_1") (pintype "passive"))
      (node (ref "U1") (pin "7") (pinfunction "VSS/VSSA_7") (pintype "passive"))
    )
    (net (code "62") (name "unconnected-(U1-PB0-Pad19)") (class "Default")
      (node (ref "U1") (pin "19") (pinfunction "PB0_19") (pintype "bidirectional"))
    )
    (net (code "63") (name "unconnected-(U1-PB6-Pad45)") (class "Default")
      (node (ref "U1") (pin "45") (pinfunction "PB6_45") (pintype "bidirectional"))
    )
    (net (code "64") (name "unconnected-(U1-PB7-Pad46)") (class "Default")
      (node (ref "U1") (pin "46") (pinfunction "PB7_46") (pintype "bidirectional"))
    )
    (net (code "65") (name "unconnected-(U1-PB14-Pad26)") (class "Default")
      (node (ref "U1") (pin "26") (pinfunction "PB14_26") (pintype "bidirectional"))
    )
    (net (code "66") (name "unconnected-(U1-PB15-Pad27)") (class "Default")
      (node (ref "U1") (pin "27") (pinfunction "PB15_27") (pintype "bidirectional"))
    )
    (net (code "67") (name "unconnected-(U1-PC15-OSC32_OUT-Pad3)") (class "Default")
      (node (ref "U1") (pin "3") (pinfunction "PC15-OSC32_OUT_3") (pintype "bidirectional"))
    )
  )
)
